# Controller_sch.net
KiCad netlist of a schematic drawn in Altium Designer
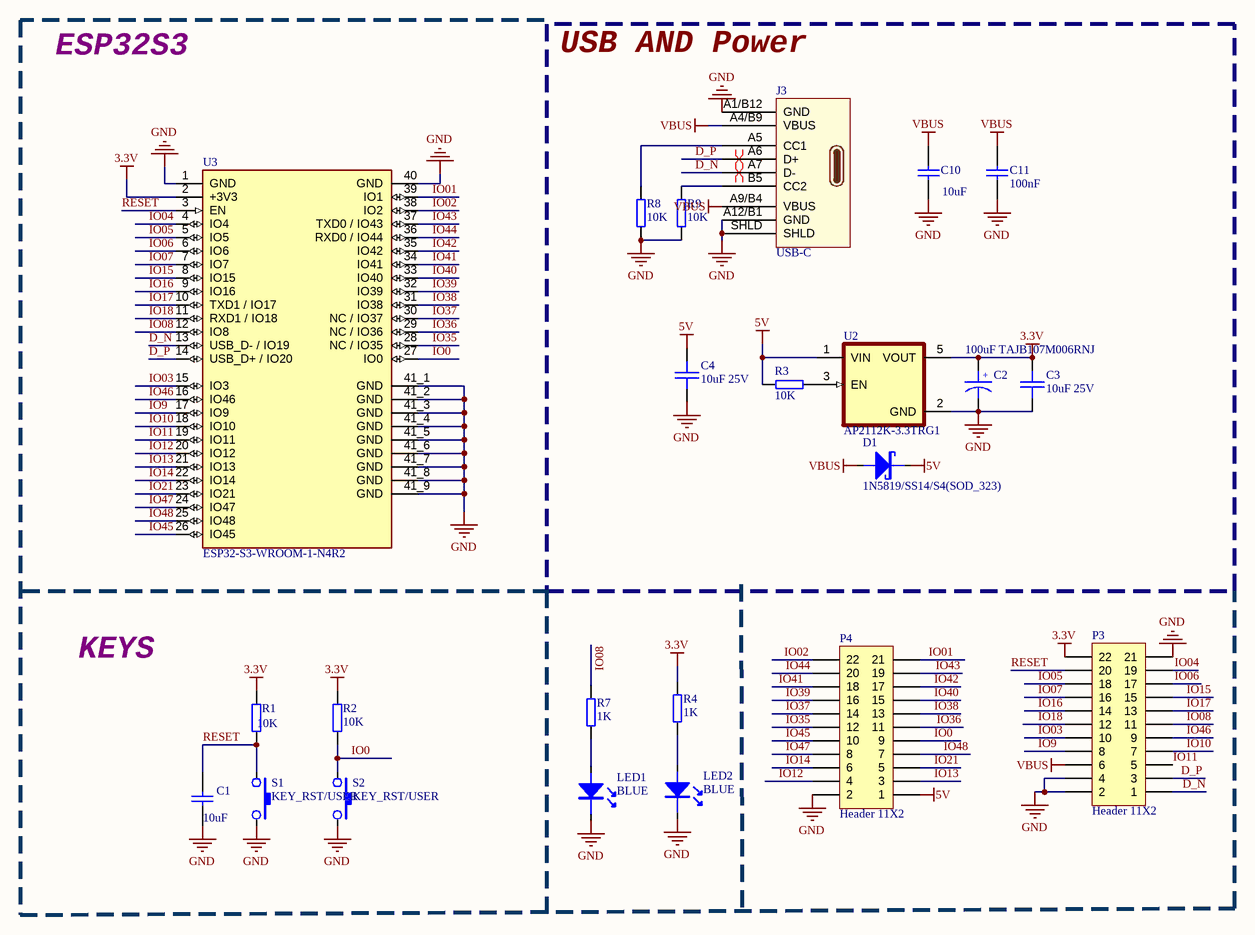
[diagram p0: Controller_sch.SchDoc]

(export (version "E")
  (design (tool "Eeschema 10.0.6"))
  (components
    (comp (ref "C1")
      (value "10uF")
      (footprint "CAPC1608X90N")
      (description "CAP SM 0603 X5R 10uF 10%")
      (fields (field (name "TOLERANCE") "±10%") (field (name "Comment") "Cap Semi"))
      (libsource (lib "electronpowered") (part "CAP-SM-0603-X5R-10uF"))
    )
    (comp (ref "C2")
      (value "100uF TAJB107M006RNJ")
      (footprint "SMT_C_Tantalum_B")
      (description "Capacitor, SM Tantalum; Body 3.5 x 2.8 mm (LxW typ)")
      (libsource (lib "NODEMCU_DEVKIT_V1.0") (part "SMT_C_Tantalum_B"))
    )
    (comp (ref "C3")
      (value "10uF 25V")
      (footprint "CAPC2012X135N")
      (description "Surface mount capacitor 0805")
      (libsource (lib "NODEMCU_DEVKIT_V1.0") (part "SMT_C_0805"))
    )
    (comp (ref "C4")
      (value "10uF 25V")
      (footprint "CAPC2012X135N")
      (description "Surface mount capacitor 0805")
      (libsource (lib "NODEMCU_DEVKIT_V1.0") (part "SMT_C_0805"))
    )
    (comp (ref "C10")
      (value "10uF")
      (footprint "CAPC1608X90N")
      (description "CAP SM 0603 X5R 10uF 10%")
      (fields (field (name "TOLERANCE") "±10%") (field (name "Comment") "Cap Semi"))
      (libsource (lib "electronpowered") (part "CAP-SM-0603-X5R-10uF"))
    )
    (comp (ref "C11")
      (value "100nF")
      (footprint "CAPC1608X90N")
      (description "CAP SM 0603 X7R 100nF 10%")
      (fields (field (name "TOLERANCE") "±10%") (field (name "Comment") "Cap Semi"))
      (libsource (lib "electronpowered") (part "CAP-SM-0603-X7R-100nF"))
    )
    (comp (ref "D1")
      (value "1N5819/SS14/S4(SOD_323)")
      (footprint "SMT_DIODE_SOD_323")
      (description "Surface mount schottky diode SOD-323(0805) Package")
      (libsource (lib "NODEMCU_DEVKIT_V1.0") (part "SMT_DIODE_SCHOTTKY_SOD_323"))
    )
    (comp (ref "J3") (value "USB-C") (footprint "USB-C 8p") (libsource (lib "Keyboard") (part "USB-C")))
    (comp (ref "LED1")
      (value "BLUE")
      (footprint "SMT_LED_0603")
      (description "SMT LED")
      (libsource (lib "NODEMCU_DEVKIT_V1.0") (part "SMT_LED_0603"))
    )
    (comp (ref "LED2")
      (value "BLUE")
      (footprint "SMT_LED_0603")
      (description "SMT LED")
      (libsource (lib "NODEMCU_DEVKIT_V1.0") (part "SMT_LED_0603"))
    )
    (comp (ref "P3")
      (value "Header 11X2")
      (footprint "HDR2X11")
      (description "Header, 11-Pin, Dual row")
      (fields (field (name "PUBLISHER") "Altium Limited"))
      (libsource (lib "My Library") (part "Header 11X2"))
    )
    (comp (ref "P4")
      (value "Header 11X2")
      (footprint "HDR2X11")
      (description "Header, 11-Pin, Dual row")
      (fields (field (name "PUBLISHER") "Altium Limited"))
      (libsource (lib "My Library") (part "Header 11X2"))
    )
    (comp (ref "R1")
      (value "10K")
      (footprint "RESC1608N_ZERO")
      (description "RES SM 0603 10K")
      (fields (field (name "Comment") "Resistor"))
      (libsource (lib "electronpowered") (part "RES-SM-0603-10K"))
    )
    (comp (ref "R2")
      (value "10K")
      (footprint "RESC1608N_ZERO")
      (description "RES SM 0603 10K")
      (fields (field (name "Comment") "Resistor"))
      (libsource (lib "electronpowered") (part "RES-SM-0603-10K"))
    )
    (comp (ref "R3")
      (value "10K")
      (footprint "RESC1608N_ZERO")
      (description "RES SM 0603 10K")
      (fields (field (name "Comment") "Resistor"))
      (libsource (lib "electronpowered") (part "RES-SM-0603-10K"))
    )
    (comp (ref "R4")
      (value "1K")
      (footprint "RESC1608N_ZERO")
      (description "RES SM 0603 1K")
      (fields (field (name "Comment") "Resistor"))
      (libsource (lib "electronpowered") (part "RES-SM-0603-1K"))
    )
    (comp (ref "R7")
      (value "1K")
      (footprint "RESC1608N_ZERO")
      (description "RES SM 0603 1K")
      (fields (field (name "Comment") "Resistor"))
      (libsource (lib "electronpowered") (part "RES-SM-0603-1K"))
    )
    (comp (ref "R8")
      (value "10K")
      (footprint "RESC1608N_ZERO")
      (description "RES SM 0603 10K")
      (fields (field (name "Comment") "Resistor"))
      (libsource (lib "electronpowered") (part "RES-SM-0603-10K"))
    )
    (comp (ref "R9")
      (value "10K")
      (footprint "RESC1608N_ZERO")
      (description "RES SM 0603 10K")
      (fields (field (name "Comment") "Resistor"))
      (libsource (lib "electronpowered") (part "RES-SM-0603-10K"))
    )
    (comp (ref "S1")
      (value "KEY_RST/USER")
      (footprint "SMT_SW_PTS_820")
      (description "SMT Tactile ‎Switch PTS 820 Series")
      (libsource (lib "NODEMCU_DEVKIT_V1.0") (part "SMT_SW_PTS_820"))
    )
    (comp (ref "S2")
      (value "KEY_RST/USER")
      (footprint "SMT_SW_PTS_820")
      (description "SMT Tactile ‎Switch PTS 820 Series")
      (libsource (lib "NODEMCU_DEVKIT_V1.0") (part "SMT_SW_PTS_820"))
    )
    (comp (ref "U2")
      (value "AP2112K-3.3TRG1")
      (footprint "SOT23-5")
      (description "Linear Voltage Regulator IC 1 Output 600mA SOT-25")
      (fields
        (field (name "DIGI-KEY_PART_NUMBER") "AP2112K-3.3TRG1DICT-ND")
        (field (name "MF") "Diodes Inc.")
      )
      (libsource (lib "AP2112K-3.3TRG1") (part "AP2112K-3.3TRG1"))
    )
    (comp (ref "U3")
      (value "ESP32-S3-WROOM-1-N4R2")
      (footprint "ESP32-S3-WROOM-1_NO-KEEPOUT")
      (fields
        (field (name "MPN") "ESP32-S3-WROOM-1-N16R2")
        (field (name "MF") "Espressif Systems")
        (field (name "DIGI-KEY_PART_NUMBER") "1965-ESP32-S3-WROOM-1-N16R2TR-ND")
      )
      (libsource (lib "PROJECT-ESP32-S3-WROOM-1-BREAKOUT") (part "ESP32-S3-WROOM-1"))
    )
  )
  (nets
    (net (code "1") (name "/D_N") (class "Default")
      (node (ref "J3") (pin "A7") (pinfunction "D-_A7") (pintype "passive"))
      (node (ref "P3") (pin "1") (pinfunction "1_1") (pintype "passive"))
      (node (ref "U3") (pin "13") (pinfunction "USB_D-_/_IO19_13") (pintype "bidirectional"))
    )
    (net (code "2") (name "/D_P") (class "Default")
      (node (ref "J3") (pin "A6") (pinfunction "D+_A6") (pintype "passive"))
      (node (ref "P3") (pin "3") (pinfunction "3_3") (pintype "passive"))
      (node (ref "U3") (pin "14") (pinfunction "USB_D+_/_IO20_14") (pintype "bidirectional"))
    )
    (net (code "3") (name "/IO0") (class "Default")
      (node (ref "P4") (pin "9") (pinfunction "9_9") (pintype "passive"))
      (node (ref "R2") (pin "1") (pinfunction "1_1") (pintype "passive"))
      (node (ref "S2") (pin "1") (pinfunction "1_1") (pintype "passive"))
      (node (ref "U3") (pin "27") (pinfunction "IO0_27") (pintype "bidirectional"))
    )
    (net (code "4") (name "/IO01") (class "Default")
      (node (ref "P4") (pin "21") (pinfunction "21_21") (pintype "passive"))
      (node (ref "U3") (pin "39") (pinfunction "IO1_39") (pintype "bidirectional"))
    )
    (net (code "5") (name "/IO02") (class "Default")
      (node (ref "P4") (pin "22") (pinfunction "22_22") (pintype "passive"))
      (node (ref "U3") (pin "38") (pinfunction "IO2_38") (pintype "bidirectional"))
    )
    (net (code "6") (name "/IO03") (class "Default")
      (node (ref "P3") (pin "10") (pinfunction "10_10") (pintype "passive"))
      (node (ref "U3") (pin "15") (pinfunction "IO3_15") (pintype "bidirectional"))
    )
    (net (code "7") (name "/IO04") (class "Default")
      (node (ref "P3") (pin "19") (pinfunction "19_19") (pintype "passive"))
      (node (ref "U3") (pin "4") (pinfunction "IO4_4") (pintype "bidirectional"))
    )
    (net (code "8") (name "/IO05") (class "Default")
      (node (ref "P3") (pin "18") (pinfunction "18_18") (pintype "passive"))
      (node (ref "U3") (pin "5") (pinfunction "IO5_5") (pintype "bidirectional"))
    )
    (net (code "9") (name "/IO06") (class "Default")
      (node (ref "P3") (pin "17") (pinfunction "17_17") (pintype "passive"))
      (node (ref "U3") (pin "6") (pinfunction "IO6_6") (pintype "bidirectional"))
    )
    (net (code "10") (name "/IO07") (class "Default")
      (node (ref "P3") (pin "16") (pinfunction "16_16") (pintype "passive"))
      (node (ref "U3") (pin "7") (pinfunction "IO7_7") (pintype "bidirectional"))
    )
    (net (code "11") (name "/IO08") (class "Default")
      (node (ref "P3") (pin "11") (pinfunction "11_11") (pintype "passive"))
      (node (ref "R7") (pin "1") (pinfunction "1_1") (pintype "passive"))
      (node (ref "U3") (pin "12") (pinfunction "IO8_12") (pintype "bidirectional"))
    )
    (net (code "12") (name "/IO9") (class "Default")
      (node (ref "P3") (pin "8") (pinfunction "8_8") (pintype "passive"))
      (node (ref "U3") (pin "17") (pinfunction "IO9_17") (pintype "bidirectional"))
    )
    (net (code "13") (name "/IO10") (class "Default")
      (node (ref "P3") (pin "7") (pinfunction "7_7") (pintype "passive"))
      (node (ref "U3") (pin "18") (pinfunction "IO10_18") (pintype "bidirectional"))
    )
    (net (code "14") (name "/IO11") (class "Default")
      (node (ref "P3") (pin "5") (pinfunction "5_5") (pintype "passive"))
      (node (ref "U3") (pin "19") (pinfunction "IO11_19") (pintype "bidirectional"))
    )
    (net (code "15") (name "/IO12") (class "Default")
      (node (ref "P4") (pin "4") (pinfunction "4_4") (pintype "passive"))
      (node (ref "U3") (pin "20") (pinfunction "IO12_20") (pintype "bidirectional"))
    )
    (net (code "16") (name "/IO13") (class "Default")
      (node (ref "P4") (pin "3") (pinfunction "3_3") (pintype "passive"))
      (node (ref "U3") (pin "21") (pinfunction "IO13_21") (pintype "bidirectional"))
    )
    (net (code "17") (name "/IO14") (class "Default")
      (node (ref "P4") (pin "6") (pinfunction "6_6") (pintype "passive"))
      (node (ref "U3") (pin "22") (pinfunction "IO14_22") (pintype "bidirectional"))
    )
    (net (code "18") (name "/IO15") (class "Default")
      (node (ref "P3") (pin "15") (pinfunction "15_15") (pintype "passive"))
      (node (ref "U3") (pin "8") (pinfunction "IO15_8") (pintype "bidirectional"))
    )
    (net (code "19") (name "/IO16") (class "Default")
      (node (ref "P3") (pin "14") (pinfunction "14_14") (pintype "passive"))
      (node (ref "U3") (pin "9") (pinfunction "IO16_9") (pintype "bidirectional"))
    )
    (net (code "20") (name "/IO17") (class "Default")
      (node (ref "P3") (pin "13") (pinfunction "13_13") (pintype "passive"))
      (node (ref "U3") (pin "10") (pinfunction "TXD1_/_IO17_10") (pintype "bidirectional"))
    )
    (net (code "21") (name "/IO18") (class "Default")
      (node (ref "P3") (pin "12") (pinfunction "12_12") (pintype "passive"))
      (node (ref "U3") (pin "11") (pinfunction "RXD1_/_IO18_11") (pintype "bidirectional"))
    )
    (net (code "22") (name "/IO21") (class "Default")
      (node (ref "P4") (pin "5") (pinfunction "5_5") (pintype "passive"))
      (node (ref "U3") (pin "23") (pinfunction "IO21_23") (pintype "bidirectional"))
    )
    (net (code "23") (name "/IO35") (class "Default")
      (node (ref "P4") (pin "12") (pinfunction "12_12") (pintype "passive"))
      (node (ref "U3") (pin "28") (pinfunction "NC_/_IO35_28") (pintype "bidirectional"))
    )
    (net (code "24") (name "/IO36") (class "Default")
      (node (ref "P4") (pin "11") (pinfunction "11_11") (pintype "passive"))
      (node (ref "U3") (pin "29") (pinfunction "NC_/_IO36_29") (pintype "bidirectional"))
    )
    (net (code "25") (name "/IO37") (class "Default")
      (node (ref "P4") (pin "14") (pinfunction "14_14") (pintype "passive"))
      (node (ref "U3") (pin "30") (pinfunction "NC_/_IO37_30") (pintype "bidirectional"))
    )
    (net (code "26") (name "/IO38") (class "Default")
      (node (ref "P4") (pin "13") (pinfunction "13_13") (pintype "passive"))
      (node (ref "U3") (pin "31") (pinfunction "IO38_31") (pintype "bidirectional"))
    )
    (net (code "27") (name "/IO39") (class "Default")
      (node (ref "P4") (pin "16") (pinfunction "16_16") (pintype "passive"))
      (node (ref "U3") (pin "32") (pinfunction "IO39_32") (pintype "bidirectional"))
    )
    (net (code "28") (name "/IO40") (class "Default")
      (node (ref "P4") (pin "15") (pinfunction "15_15") (pintype "passive"))
      (node (ref "U3") (pin "33") (pinfunction "IO40_33") (pintype "bidirectional"))
    )
    (net (code "29") (name "/IO41") (class "Default")
      (node (ref "P4") (pin "18") (pinfunction "18_18") (pintype "passive"))
      (node (ref "U3") (pin "34") (pinfunction "IO41_34") (pintype "bidirectional"))
    )
    (net (code "30") (name "/IO42") (class "Default")
      (node (ref "P4") (pin "17") (pinfunction "17_17") (pintype "passive"))
      (node (ref "U3") (pin "35") (pinfunction "IO42_35") (pintype "bidirectional"))
    )
    (net (code "31") (name "/IO43") (class "Default")
      (node (ref "P4") (pin "19") (pinfunction "19_19") (pintype "passive"))
      (node (ref "U3") (pin "37") (pinfunction "TXD0_/_IO43_37") (pintype "bidirectional"))
    )
    (net (code "32") (name "/IO44") (class "Default")
      (node (ref "P4") (pin "20") (pinfunction "20_20") (pintype "passive"))
      (node (ref "U3") (pin "36") (pinfunction "RXD0_/_IO44_36") (pintype "bidirectional"))
    )
    (net (code "33") (name "/IO45") (class "Default")
      (node (ref "P4") (pin "10") (pinfunction "10_10") (pintype "passive"))
      (node (ref "U3") (pin "26") (pinfunction "IO45_26") (pintype "bidirectional"))
    )
    (net (code "34") (name "/IO46") (class "Default")
      (node (ref "P3") (pin "9") (pinfunction "9_9") (pintype "passive"))
      (node (ref "U3") (pin "16") (pinfunction "IO46_16") (pintype "bidirectional"))
    )
    (net (code "35") (name "/IO47") (class "Default")
      (node (ref "P4") (pin "8") (pinfunction "8_8") (pintype "passive"))
      (node (ref "U3") (pin "24") (pinfunction "IO47_24") (pintype "bidirectional"))
    )
    (net (code "36") (name "/IO48") (class "Default")
      (node (ref "P4") (pin "7") (pinfunction "7_7") (pintype "passive"))
      (node (ref "U3") (pin "25") (pinfunction "IO48_25") (pintype "bidirectional"))
    )
    (net (code "37") (name "/RESET") (class "Default")
      (node (ref "C1") (pin "2") (pinfunction "2_2") (pintype "passive"))
      (node (ref "P3") (pin "20") (pinfunction "20_20") (pintype "passive"))
      (node (ref "R1") (pin "1") (pinfunction "1_1") (pintype "passive"))
      (node (ref "S1") (pin "1") (pinfunction "1_1") (pintype "passive"))
      (node (ref "U3") (pin "3") (pinfunction "EN_3") (pintype "input"))
    )
    (net (code "38") (name "3.3V") (class "Default")
      (node (ref "C2") (pin "1") (pinfunction "1_1") (pintype "passive"))
      (node (ref "C3") (pin "1") (pinfunction "1_1") (pintype "passive"))
      (node (ref "P3") (pin "22") (pinfunction "22_22") (pintype "passive"))
      (node (ref "R1") (pin "2") (pinfunction "2_2") (pintype "passive"))
      (node (ref "R2") (pin "2") (pinfunction "2_2") (pintype "passive"))
      (node (ref "R4") (pin "1") (pinfunction "1_1") (pintype "passive"))
      (node (ref "U2") (pin "5") (pinfunction "VOUT_5") (pintype "power_in"))
      (node (ref "U3") (pin "2") (pinfunction "+3V3_2") (pintype "power_in"))
    )
    (net (code "39") (name "5V") (class "Default")
      (node (ref "C4") (pin "1") (pinfunction "1_1") (pintype "passive"))
      (node (ref "D1") (pin "2") (pinfunction "K_2") (pintype "passive"))
      (node (ref "P4") (pin "1") (pinfunction "1_1") (pintype "passive"))
      (node (ref "R3") (pin "2") (pinfunction "2_2") (pintype "passive"))
      (node (ref "U2") (pin "1") (pinfunction "VIN_1") (pintype "power_in"))
    )
    (net (code "40") (name "GND") (class "Default")
      (node (ref "C1") (pin "1") (pinfunction "1_1") (pintype "passive"))
      (node (ref "C10") (pin "1") (pinfunction "1_1") (pintype "passive"))
      (node (ref "C11") (pin "2") (pinfunction "2_2") (pintype "passive"))
      (node (ref "C2") (pin "2") (pinfunction "2_2") (pintype "passive"))
      (node (ref "C3") (pin "2") (pinfunction "2_2") (pintype "passive"))
      (node (ref "C4") (pin "2") (pinfunction "2_2") (pintype "passive"))
      (node (ref "J3") (pin "A1/B12") (pinfunction "GND_A1/B12") (pintype "passive"))
      (node (ref "J3") (pin "A12/B1") (pinfunction "GND_A12/B1") (pintype "passive"))
      (node (ref "J3") (pin "SHLD") (pinfunction "SHLD_SHLD") (pintype "passive"))
      (node (ref "LED1") (pin "2") (pinfunction "K_2") (pintype "passive"))
      (node (ref "LED2") (pin "2") (pinfunction "K_2") (pintype "passive"))
      (node (ref "P3") (pin "2") (pinfunction "2_2") (pintype "passive"))
      (node (ref "P3") (pin "21") (pinfunction "21_21") (pintype "passive"))
      (node (ref "P3") (pin "4") (pinfunction "4_4") (pintype "passive"))
      (node (ref "P4") (pin "2") (pinfunction "2_2") (pintype "passive"))
      (node (ref "R8") (pin "1") (pinfunction "1_1") (pintype "passive"))
      (node (ref "R9") (pin "2") (pinfunction "2_2") (pintype "passive"))
      (node (ref "S1") (pin "2") (pinfunction "2_2") (pintype "passive"))
      (node (ref "S2") (pin "2") (pinfunction "2_2") (pintype "passive"))
      (node (ref "U2") (pin "2") (pinfunction "GND_2") (pintype "power_in"))
      (node (ref "U3") (pin "1") (pinfunction "GND_1") (pintype "power_in"))
      (node (ref "U3") (pin "40") (pinfunction "GND_40") (pintype "power_in"))
      (node (ref "U3") (pin "41_1") (pinfunction "GND_41_1") (pintype "power_in"))
      (node (ref "U3") (pin "41_2") (pinfunction "GND_41_2") (pintype "power_in"))
      (node (ref "U3") (pin "41_3") (pinfunction "GND_41_3") (pintype "power_in"))
      (node (ref "U3") (pin "41_4") (pinfunction "GND_41_4") (pintype "power_in"))
      (node (ref "U3") (pin "41_5") (pinfunction "GND_41_5") (pintype "power_in"))
      (node (ref "U3") (pin "41_6") (pinfunction "GND_41_6") (pintype "power_in"))
      (node (ref "U3") (pin "41_7") (pinfunction "GND_41_7") (pintype "power_in"))
      (node (ref "U3") (pin "41_8") (pinfunction "GND_41_8") (pintype "power_in"))
      (node (ref "U3") (pin "41_9") (pinfunction "GND_41_9") (pintype "power_in"))
    )
    (net (code "41") (name "Net-(J3-CC1)") (class "Default")
      (node (ref "J3") (pin "A5") (pinfunction "CC1_A5") (pintype "passive"))
      (node (ref "R8") (pin "2") (pinfunction "2_2") (pintype "passive"))
    )
    (net (code "42") (name "Net-(J3-CC2)") (class "Default")
      (node (ref "J3") (pin "B5") (pinfunction "CC2_B5") (pintype "passive"))
      (node (ref "R9") (pin "1") (pinfunction "1_1") (pintype "passive"))
    )
    (net (code "43") (name "Net-(LED1-A)") (class "Default")
      (node (ref "LED1") (pin "1") (pinfunction "A_1") (pintype "passive"))
      (node (ref "R7") (pin "2") (pinfunction "2_2") (pintype "passive"))
    )
    (net (code "44") (name "Net-(LED2-A)") (class "Default")
      (node (ref "LED2") (pin "1") (pinfunction "A_1") (pintype "passive"))
      (node (ref "R4") (pin "2") (pinfunction "2_2") (pintype "passive"))
    )
    (net (code "45") (name "Net-(U2-EN)") (class "Default")
      (node (ref "R3") (pin "1") (pinfunction "1_1") (pintype "passive"))
      (node (ref "U2") (pin "3") (pinfunction "EN_3") (pintype "input"))
    )
    (net (code "46") (name "VBUS") (class "Default")
      (node (ref "C10") (pin "2") (pinfunction "2_2") (pintype "passive"))
      (node (ref "C11") (pin "1") (pinfunction "1_1") (pintype "passive"))
      (node (ref "D1") (pin "1") (pinfunction "A_1") (pintype "passive"))
      (node (ref "J3") (pin "A4/B9") (pinfunction "VBUS_A4/B9") (pintype "passive"))
      (node (ref "J3") (pin "A9/B4") (pinfunction "VBUS_A9/B4") (pintype "passive"))
      (node (ref "P3") (pin "6") (pinfunction "6_6") (pintype "passive"))
    )
  )
)
